# mainboardv0_1.net
KiCad netlist of a schematic drawn in EAGLE
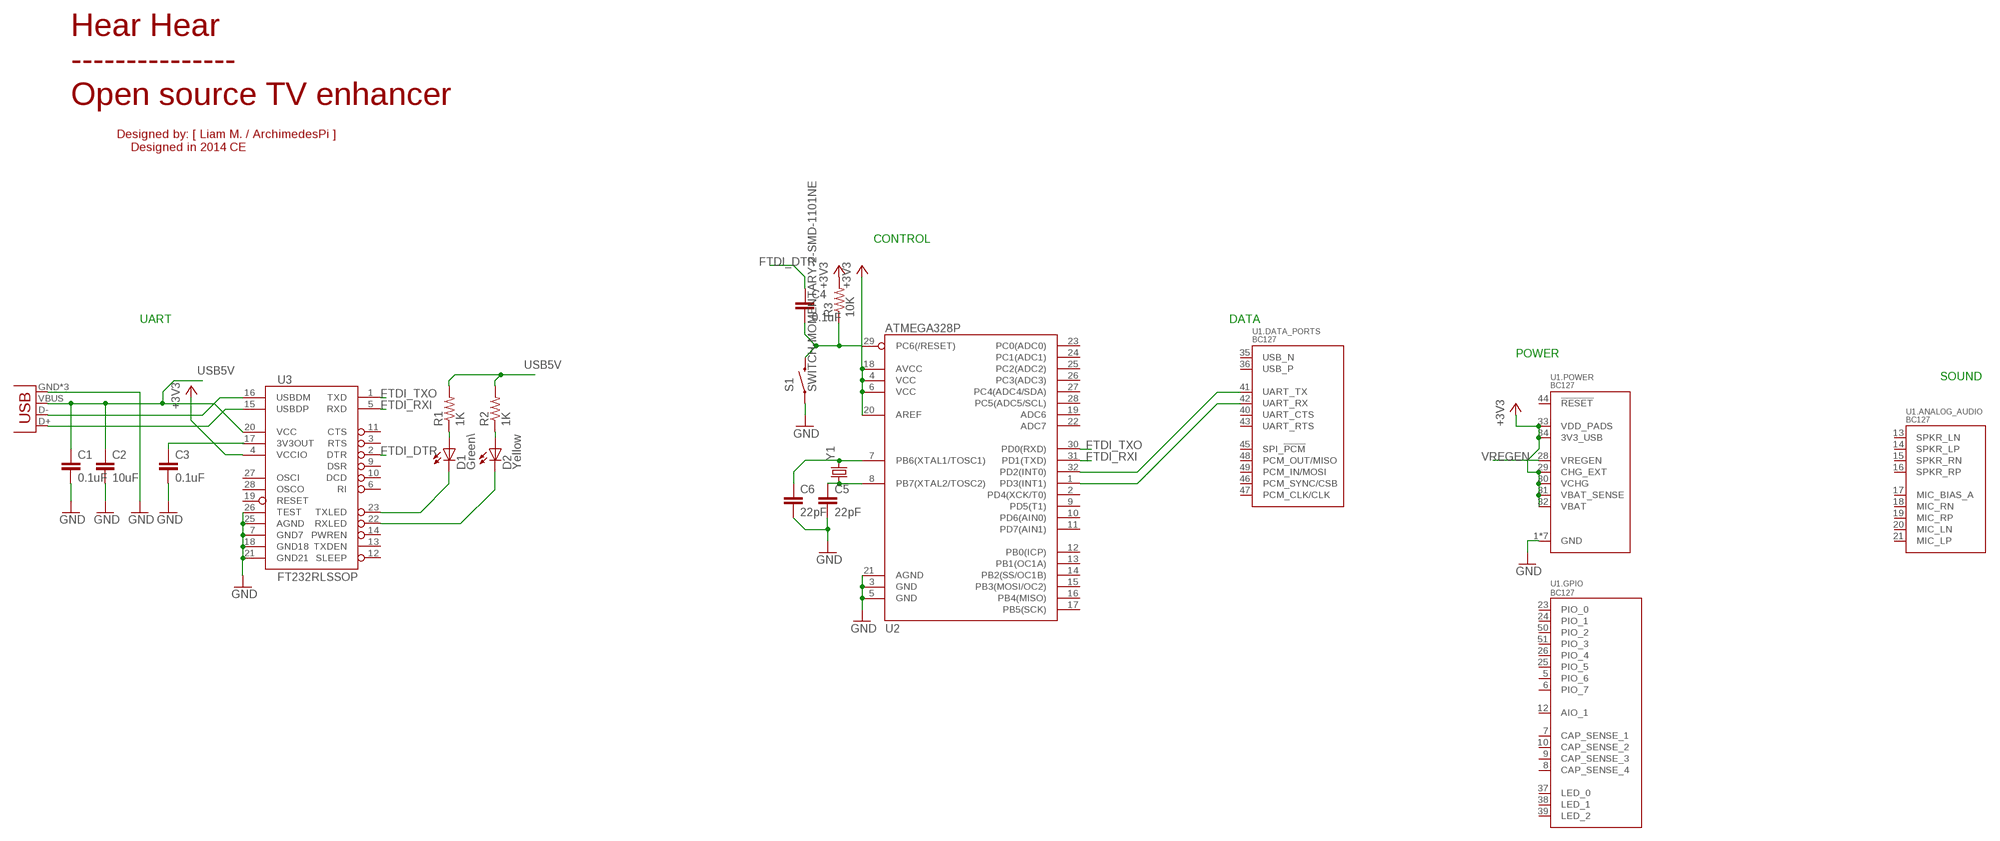
[diagram p0: schematic, sheet 1]

(export (version "E")
  (design (tool "Eeschema 10.0.6"))
  (components
    (comp (ref "C1")
      (value "0.1uF")
      (footprint "eagle-import:0603-CAP")
      (libsource (lib "eagle-import") (part "0.1UF-100V-10%(0603)"))
    )
    (comp (ref "C2")
      (value "10uF")
      (footprint "eagle-import:0603-CAP")
      (libsource (lib "eagle-import") (part "10UF-6.3V-20%(0603)"))
    )
    (comp (ref "C3")
      (value "0.1uF")
      (footprint "eagle-import:0603-CAP")
      (libsource (lib "eagle-import") (part "0.1UF-100V-10%(0603)"))
    )
    (comp (ref "C4")
      (value "0.1uF")
      (footprint "eagle-import:0603-CAP")
      (libsource (lib "eagle-import") (part "0.1UF-25V(+80/-20%)(0603)"))
    )
    (comp (ref "C5")
      (value "22pF")
      (footprint "eagle-import:0603-CAP")
      (libsource (lib "eagle-import") (part "22PF-50V-5%(0603)"))
    )
    (comp (ref "C6")
      (value "22pF")
      (footprint "eagle-import:0603-CAP")
      (libsource (lib "eagle-import") (part "22PF-50V-5%(0603)"))
    )
    (comp (ref "D1")
      (value "Green\\")
      (footprint "eagle-import:LED-0603")
      (libsource (lib "eagle-import") (part "LED-GREEN0603"))
    )
    (comp (ref "D2")
      (value "Yellow")
      (footprint "eagle-import:LED-0603")
      (libsource (lib "eagle-import") (part "LED-YELLOW0603"))
    )
    (comp (ref "JP1")
      (value "USB-MICROB")
      (footprint "eagle-import:USB-MICROB")
      (libsource (lib "eagle-import") (part "USB-MICROB"))
    )
    (comp (ref "R1")
      (value "1K")
      (footprint "eagle-import:0603-RES")
      (libsource (lib "eagle-import") (part "1KOHM1/10W1%(0603)"))
    )
    (comp (ref "R2")
      (value "1K")
      (footprint "eagle-import:0603-RES")
      (libsource (lib "eagle-import") (part "1KOHM1/10W1%(0603)"))
    )
    (comp (ref "R3")
      (value "10K")
      (footprint "eagle-import:0603-RES")
      (libsource (lib "eagle-import") (part "10KOHM1/10W1%(0603)0603"))
    )
    (comp (ref "S1")
      (value "SWITCH-MOMENTARY-2-SMD-1101NE")
      (footprint "eagle-import:TACTILE-SWITCH-1101NE")
      (libsource (lib "eagle-import") (part "SWITCH-MOMENTARY-2-SMD-1101NE"))
    )
    (comp (ref "U1")
      (value "BC127")
      (footprint "eagle-import:BC127")
      (libsource (lib "eagle-import") (part "BC127"))
    )
    (comp (ref "U2")
      (value "ATMEGA328P")
      (footprint "eagle-import:TQFP32-08")
      (libsource (lib "eagle-import") (part "ATMEGA328_SMT"))
    )
    (comp (ref "U3")
      (value "FT232RLSSOP")
      (footprint "eagle-import:SSOP28DB")
      (libsource (lib "eagle-import") (part "FT232RLSSOP"))
    )
    (comp (ref "Y1")
      (value "CRYSTALHC49US")
      (footprint "eagle-import:HC49US")
      (libsource (lib "eagle-import") (part "CRYSTALHC49US"))
    )
  )
  (nets
    (net (code "1") (name "+3V3") (class "Default")
      (node (ref "R3") (pin "2") (pinfunction "2_2") (pintype "passive"))
      (node (ref "U1") (pin "29") (pinfunction "CHG_EXT_29") (pintype "bidirectional"))
      (node (ref "U1") (pin "30") (pinfunction "VCHG_30") (pintype "bidirectional"))
      (node (ref "U1") (pin "31") (pinfunction "VBAT_SENSE_31") (pintype "bidirectional"))
      (node (ref "U1") (pin "32") (pinfunction "VBAT_32") (pintype "bidirectional"))
      (node (ref "U1") (pin "33") (pinfunction "VDD_PADS_33") (pintype "bidirectional"))
      (node (ref "U1") (pin "34") (pinfunction "3V3_USB_34") (pintype "bidirectional"))
      (node (ref "U2") (pin "18") (pinfunction "AVCC_18") (pintype "bidirectional"))
      (node (ref "U2") (pin "20") (pinfunction "AREF_20") (pintype "bidirectional"))
      (node (ref "U2") (pin "4") (pinfunction "VCC_4") (pintype "bidirectional"))
      (node (ref "U2") (pin "6") (pinfunction "VCC_6") (pintype "bidirectional"))
      (node (ref "U3") (pin "4") (pinfunction "VCCIO_4") (pintype "power_in"))
    )
    (net (code "2") (name "/FTDI_DTR") (class "Default")
      (node (ref "C4") (pin "1") (pinfunction "1_1") (pintype "passive"))
      (node (ref "U3") (pin "2") (pinfunction "DTR_2") (pintype "output"))
    )
    (net (code "3") (name "/FTDI_RXI") (class "Default")
      (node (ref "U2") (pin "31") (pinfunction "PD1(TXD)_31") (pintype "bidirectional"))
      (node (ref "U3") (pin "5") (pinfunction "RXD_5") (pintype "input"))
    )
    (net (code "4") (name "/FTDI_TXO") (class "Default")
      (node (ref "U2") (pin "30") (pinfunction "PD0(RXD)_30") (pintype "bidirectional"))
      (node (ref "U3") (pin "1") (pinfunction "TXD_1") (pintype "output"))
    )
    (net (code "5") (name "/USB5V") (class "Default")
      (node (ref "C1") (pin "1") (pinfunction "1_1") (pintype "passive"))
      (node (ref "C2") (pin "1") (pinfunction "1_1") (pintype "passive"))
      (node (ref "JP1") (pin "VBUS") (pinfunction "VBUS_VBUS") (pintype "bidirectional"))
      (node (ref "R1") (pin "2") (pinfunction "2_2") (pintype "passive"))
      (node (ref "R2") (pin "2") (pinfunction "2_2") (pintype "passive"))
      (node (ref "U3") (pin "20") (pinfunction "VCC_20") (pintype "power_in"))
    )
    (net (code "6") (name "/VREGEN") (class "Default")
      (node (ref "U1") (pin "28") (pinfunction "VREGEN_28") (pintype "bidirectional"))
    )
    (net (code "7") (name "GND") (class "Default")
      (node (ref "C1") (pin "2") (pinfunction "2_2") (pintype "passive"))
      (node (ref "C2") (pin "2") (pinfunction "2_2") (pintype "passive"))
      (node (ref "C3") (pin "2") (pinfunction "2_2") (pintype "passive"))
      (node (ref "C5") (pin "2") (pinfunction "2_2") (pintype "passive"))
      (node (ref "C6") (pin "2") (pinfunction "2_2") (pintype "passive"))
      (node (ref "JP1") (pin "GND") (pinfunction "GND_GND") (pintype "bidirectional"))
      (node (ref "JP1") (pin "MT1") (pinfunction "GND_MT1") (pintype "bidirectional"))
      (node (ref "JP1") (pin "MT2") (pinfunction "GND_MT2") (pintype "bidirectional"))
      (node (ref "S1") (pin "P$1") (pinfunction "1_P$1") (pintype "passive"))
      (node (ref "U1") (pin "1") (pinfunction "GND_1") (pintype "bidirectional"))
      (node (ref "U1") (pin "11") (pinfunction "GND_11") (pintype "bidirectional"))
      (node (ref "U1") (pin "2") (pinfunction "GND_2") (pintype "bidirectional"))
      (node (ref "U1") (pin "22") (pinfunction "GND_22") (pintype "bidirectional"))
      (node (ref "U1") (pin "27") (pinfunction "GND_27") (pintype "bidirectional"))
      (node (ref "U1") (pin "3") (pinfunction "GND_3") (pintype "bidirectional"))
      (node (ref "U1") (pin "4") (pinfunction "GND_4") (pintype "bidirectional"))
      (node (ref "U2") (pin "21") (pinfunction "AGND_21") (pintype "bidirectional"))
      (node (ref "U2") (pin "3") (pinfunction "GND_3") (pintype "bidirectional"))
      (node (ref "U2") (pin "5") (pinfunction "GND_5") (pintype "bidirectional"))
      (node (ref "U3") (pin "18") (pinfunction "GND18_18") (pintype "power_in"))
      (node (ref "U3") (pin "21") (pinfunction "GND21_21") (pintype "power_in"))
      (node (ref "U3") (pin "25") (pinfunction "AGND_25") (pintype "power_in"))
      (node (ref "U3") (pin "26") (pinfunction "TEST_26") (pintype "input"))
      (node (ref "U3") (pin "7") (pinfunction "GND7_7") (pintype "power_in"))
    )
    (net (code "8") (name "Net-(D1-PadA)") (class "Default")
      (node (ref "D1") (pin "A") (pinfunction "A_A") (pintype "passive"))
      (node (ref "R1") (pin "1") (pinfunction "1_1") (pintype "passive"))
    )
    (net (code "9") (name "Net-(D2-PadA)") (class "Default")
      (node (ref "D2") (pin "A") (pinfunction "A_A") (pintype "passive"))
      (node (ref "R2") (pin "1") (pinfunction "1_1") (pintype "passive"))
    )
    (net (code "10") (name "Net-(S1-2)") (class "Default")
      (node (ref "C4") (pin "2") (pinfunction "2_2") (pintype "passive"))
      (node (ref "R3") (pin "1") (pinfunction "1_1") (pintype "passive"))
      (node (ref "S1") (pin "P$2") (pinfunction "2_P$2") (pintype "passive"))
      (node (ref "U2") (pin "29") (pinfunction "PC6(/RESET)_29") (pintype "bidirectional"))
    )
    (net (code "11") (name "Net-(U1B-UART_RX)") (class "Default")
      (node (ref "U1") (pin "42") (pinfunction "UART_RX_42") (pintype "bidirectional"))
      (node (ref "U2") (pin "1") (pinfunction "PD3(INT1)_1") (pintype "bidirectional"))
    )
    (net (code "12") (name "Net-(U1B-UART_TX)") (class "Default")
      (node (ref "U1") (pin "41") (pinfunction "UART_TX_41") (pintype "bidirectional"))
      (node (ref "U2") (pin "32") (pinfunction "PD2(INT0)_32") (pintype "bidirectional"))
    )
    (net (code "13") (name "Net-(U2-PB6(XTAL1{slash}TOSC1))") (class "Default")
      (node (ref "C6") (pin "1") (pinfunction "1_1") (pintype "passive"))
      (node (ref "U2") (pin "7") (pinfunction "PB6(XTAL1/TOSC1)_7") (pintype "bidirectional"))
      (node (ref "Y1") (pin "2") (pinfunction "2_2") (pintype "passive"))
    )
    (net (code "14") (name "Net-(U2-PB7(XTAL2{slash}TOSC2))") (class "Default")
      (node (ref "C5") (pin "1") (pinfunction "1_1") (pintype "passive"))
      (node (ref "U2") (pin "8") (pinfunction "PB7(XTAL2/TOSC2)_8") (pintype "bidirectional"))
      (node (ref "Y1") (pin "1") (pinfunction "1_1") (pintype "passive"))
    )
    (net (code "15") (name "Net-(U3-3V3OUT)") (class "Default")
      (node (ref "C3") (pin "1") (pinfunction "1_1") (pintype "passive"))
      (node (ref "U3") (pin "17") (pinfunction "3V3OUT_17") (pintype "output"))
    )
    (net (code "16") (name "Net-(U3-RXLED)") (class "Default")
      (node (ref "D2") (pin "C") (pinfunction "C_C") (pintype "passive"))
      (node (ref "U3") (pin "22") (pinfunction "RXLED_22") (pintype "input"))
    )
    (net (code "17") (name "Net-(U3-TXLED)") (class "Default")
      (node (ref "D1") (pin "C") (pinfunction "C_C") (pintype "passive"))
      (node (ref "U3") (pin "23") (pinfunction "TXLED_23") (pintype "input"))
    )
    (net (code "18") (name "Net-(U3-USBDM)") (class "Default")
      (node (ref "JP1") (pin "D-") (pinfunction "D-_D-") (pintype "bidirectional"))
      (node (ref "U3") (pin "16") (pinfunction "USBDM_16") (pintype "bidirectional"))
    )
    (net (code "19") (name "Net-(U3-USBDP)") (class "Default")
      (node (ref "JP1") (pin "D+") (pinfunction "D+_D+") (pintype "bidirectional"))
      (node (ref "U3") (pin "15") (pinfunction "USBDP_15") (pintype "bidirectional"))
    )
    (net (code "20") (name "unconnected-(U1A-MIC_BIAS_A-Pad17)") (class "Default")
      (node (ref "U1") (pin "17") (pinfunction "MIC_BIAS_A_17") (pintype "bidirectional"))
    )
    (net (code "21") (name "unconnected-(U1A-MIC_LN-Pad20)") (class "Default")
      (node (ref "U1") (pin "20") (pinfunction "MIC_LN_20") (pintype "bidirectional"))
    )
    (net (code "22") (name "unconnected-(U1A-MIC_LP-Pad21)") (class "Default")
      (node (ref "U1") (pin "21") (pinfunction "MIC_LP_21") (pintype "bidirectional"))
    )
    (net (code "23") (name "unconnected-(U1A-MIC_RN-Pad18)") (class "Default")
      (node (ref "U1") (pin "18") (pinfunction "MIC_RN_18") (pintype "bidirectional"))
    )
    (net (code "24") (name "unconnected-(U1A-MIC_RP-Pad19)") (class "Default")
      (node (ref "U1") (pin "19") (pinfunction "MIC_RP_19") (pintype "bidirectional"))
    )
    (net (code "25") (name "unconnected-(U1A-SPKR_LN-Pad13)") (class "Default")
      (node (ref "U1") (pin "13") (pinfunction "SPKR_LN_13") (pintype "bidirectional"))
    )
    (net (code "26") (name "unconnected-(U1A-SPKR_LP-Pad14)") (class "Default")
      (node (ref "U1") (pin "14") (pinfunction "SPKR_LP_14") (pintype "bidirectional"))
    )
    (net (code "27") (name "unconnected-(U1A-SPKR_RN-Pad15)") (class "Default")
      (node (ref "U1") (pin "15") (pinfunction "SPKR_RN_15") (pintype "bidirectional"))
    )
    (net (code "28") (name "unconnected-(U1A-SPKR_RP-Pad16)") (class "Default")
      (node (ref "U1") (pin "16") (pinfunction "SPKR_RP_16") (pintype "bidirectional"))
    )
    (net (code "29") (name "unconnected-(U1B-PCM_CLK{slash}CLK-Pad47)") (class "Default")
      (node (ref "U1") (pin "47") (pinfunction "PCM_CLK/CLK_47") (pintype "bidirectional"))
    )
    (net (code "30") (name "unconnected-(U1B-PCM_IN{slash}MOSI-Pad49)") (class "Default")
      (node (ref "U1") (pin "49") (pinfunction "PCM_IN/MOSI_49") (pintype "bidirectional"))
    )
    (net (code "31") (name "unconnected-(U1B-PCM_OUT{slash}MISO-Pad48)") (class "Default")
      (node (ref "U1") (pin "48") (pinfunction "PCM_OUT/MISO_48") (pintype "bidirectional"))
    )
    (net (code "32") (name "unconnected-(U1B-PCM_SYNC{slash}CSB-Pad46)") (class "Default")
      (node (ref "U1") (pin "46") (pinfunction "PCM_SYNC/CSB_46") (pintype "bidirectional"))
    )
    (net (code "33") (name "unconnected-(U1B-SPI_~{PCM}-Pad45)") (class "Default")
      (node (ref "U1") (pin "45") (pinfunction "SPI_~{PCM}_45") (pintype "bidirectional"))
    )
    (net (code "34") (name "unconnected-(U1B-UART_CTS-Pad40)") (class "Default")
      (node (ref "U1") (pin "40") (pinfunction "UART_CTS_40") (pintype "bidirectional"))
    )
    (net (code "35") (name "unconnected-(U1B-UART_RTS-Pad43)") (class "Default")
      (node (ref "U1") (pin "43") (pinfunction "UART_RTS_43") (pintype "bidirectional"))
    )
    (net (code "36") (name "unconnected-(U1B-USB_N-Pad35)") (class "Default")
      (node (ref "U1") (pin "35") (pinfunction "USB_N_35") (pintype "bidirectional"))
    )
    (net (code "37") (name "unconnected-(U1B-USB_P-Pad36)") (class "Default")
      (node (ref "U1") (pin "36") (pinfunction "USB_P_36") (pintype "bidirectional"))
    )
    (net (code "38") (name "unconnected-(U1C-AIO_1-Pad12)") (class "Default")
      (node (ref "U1") (pin "12") (pinfunction "AIO_1_12") (pintype "bidirectional"))
    )
    (net (code "39") (name "unconnected-(U1C-CAP_SENSE_1-Pad7)") (class "Default")
      (node (ref "U1") (pin "7") (pinfunction "CAP_SENSE_1_7") (pintype "bidirectional"))
    )
    (net (code "40") (name "unconnected-(U1C-CAP_SENSE_2-Pad10)") (class "Default")
      (node (ref "U1") (pin "10") (pinfunction "CAP_SENSE_2_10") (pintype "bidirectional"))
    )
    (net (code "41") (name "unconnected-(U1C-CAP_SENSE_3-Pad9)") (class "Default")
      (node (ref "U1") (pin "9") (pinfunction "CAP_SENSE_3_9") (pintype "bidirectional"))
    )
    (net (code "42") (name "unconnected-(U1C-CAP_SENSE_4-Pad8)") (class "Default")
      (node (ref "U1") (pin "8") (pinfunction "CAP_SENSE_4_8") (pintype "bidirectional"))
    )
    (net (code "43") (name "unconnected-(U1C-LED_0-Pad37)") (class "Default")
      (node (ref "U1") (pin "37") (pinfunction "LED_0_37") (pintype "bidirectional"))
    )
    (net (code "44") (name "unconnected-(U1C-LED_1-Pad38)") (class "Default")
      (node (ref "U1") (pin "38") (pinfunction "LED_1_38") (pintype "bidirectional"))
    )
    (net (code "45") (name "unconnected-(U1C-LED_2-Pad39)") (class "Default")
      (node (ref "U1") (pin "39") (pinfunction "LED_2_39") (pintype "bidirectional"))
    )
    (net (code "46") (name "unconnected-(U1C-PIO_0-Pad23)") (class "Default")
      (node (ref "U1") (pin "23") (pinfunction "PIO_0_23") (pintype "bidirectional"))
    )
    (net (code "47") (name "unconnected-(U1C-PIO_1-Pad24)") (class "Default")
      (node (ref "U1") (pin "24") (pinfunction "PIO_1_24") (pintype "bidirectional"))
    )
    (net (code "48") (name "unconnected-(U1C-PIO_2-Pad50)") (class "Default")
      (node (ref "U1") (pin "50") (pinfunction "PIO_2_50") (pintype "bidirectional"))
    )
    (net (code "49") (name "unconnected-(U1C-PIO_3-Pad51)") (class "Default")
      (node (ref "U1") (pin "51") (pinfunction "PIO_3_51") (pintype "bidirectional"))
    )
    (net (code "50") (name "unconnected-(U1C-PIO_4-Pad26)") (class "Default")
      (node (ref "U1") (pin "26") (pinfunction "PIO_4_26") (pintype "bidirectional"))
    )
    (net (code "51") (name "unconnected-(U1C-PIO_5-Pad25)") (class "Default")
      (node (ref "U1") (pin "25") (pinfunction "PIO_5_25") (pintype "bidirectional"))
    )
    (net (code "52") (name "unconnected-(U1C-PIO_6-Pad5)") (class "Default")
      (node (ref "U1") (pin "5") (pinfunction "PIO_6_5") (pintype "bidirectional"))
    )
    (net (code "53") (name "unconnected-(U1C-PIO_7-Pad6)") (class "Default")
      (node (ref "U1") (pin "6") (pinfunction "PIO_7_6") (pintype "bidirectional"))
    )
    (net (code "54") (name "unconnected-(U1D-~{RESET}-Pad44)") (class "Default")
      (node (ref "U1") (pin "44") (pinfunction "~{RESET}_44") (pintype "bidirectional"))
    )
    (net (code "55") (name "unconnected-(U2-ADC6-Pad19)") (class "Default")
      (node (ref "U2") (pin "19") (pinfunction "ADC6_19") (pintype "bidirectional"))
    )
    (net (code "56") (name "unconnected-(U2-ADC7-Pad22)") (class "Default")
      (node (ref "U2") (pin "22") (pinfunction "ADC7_22") (pintype "bidirectional"))
    )
    (net (code "57") (name "unconnected-(U2-PB0(ICP)-Pad12)") (class "Default")
      (node (ref "U2") (pin "12") (pinfunction "PB0(ICP)_12") (pintype "bidirectional"))
    )
    (net (code "58") (name "unconnected-(U2-PB1(OC1A)-Pad13)") (class "Default")
      (node (ref "U2") (pin "13") (pinfunction "PB1(OC1A)_13") (pintype "bidirectional"))
    )
    (net (code "59") (name "unconnected-(U2-PB2(SS{slash}OC1B)-Pad14)") (class "Default")
      (node (ref "U2") (pin "14") (pinfunction "PB2(SS/OC1B)_14") (pintype "bidirectional"))
    )
    (net (code "60") (name "unconnected-(U2-PB3(MOSI{slash}OC2)-Pad15)") (class "Default")
      (node (ref "U2") (pin "15") (pinfunction "PB3(MOSI/OC2)_15") (pintype "bidirectional"))
    )
    (net (code "61") (name "unconnected-(U2-PB4(MISO)-Pad16)") (class "Default")
      (node (ref "U2") (pin "16") (pinfunction "PB4(MISO)_16") (pintype "bidirectional"))
    )
    (net (code "62") (name "unconnected-(U2-PB5(SCK)-Pad17)") (class "Default")
      (node (ref "U2") (pin "17") (pinfunction "PB5(SCK)_17") (pintype "bidirectional"))
    )
    (net (code "63") (name "unconnected-(U2-PC0(ADC0)-Pad23)") (class "Default")
      (node (ref "U2") (pin "23") (pinfunction "PC0(ADC0)_23") (pintype "bidirectional"))
    )
    (net (code "64") (name "unconnected-(U2-PC1(ADC1)-Pad24)") (class "Default")
      (node (ref "U2") (pin "24") (pinfunction "PC1(ADC1)_24") (pintype "bidirectional"))
    )
    (net (code "65") (name "unconnected-(U2-PC2(ADC2)-Pad25)") (class "Default")
      (node (ref "U2") (pin "25") (pinfunction "PC2(ADC2)_25") (pintype "bidirectional"))
    )
    (net (code "66") (name "unconnected-(U2-PC3(ADC3)-Pad26)") (class "Default")
      (node (ref "U2") (pin "26") (pinfunction "PC3(ADC3)_26") (pintype "bidirectional"))
    )
    (net (code "67") (name "unconnected-(U2-PC4(ADC4{slash}SDA)-Pad27)") (class "Default")
      (node (ref "U2") (pin "27") (pinfunction "PC4(ADC4/SDA)_27") (pintype "bidirectional"))
    )
    (net (code "68") (name "unconnected-(U2-PC5(ADC5{slash}SCL)-Pad28)") (class "Default")
      (node (ref "U2") (pin "28") (pinfunction "PC5(ADC5/SCL)_28") (pintype "bidirectional"))
    )
    (net (code "69") (name "unconnected-(U2-PD4(XCK{slash}T0)-Pad2)") (class "Default")
      (node (ref "U2") (pin "2") (pinfunction "PD4(XCK/T0)_2") (pintype "bidirectional"))
    )
    (net (code "70") (name "unconnected-(U2-PD5(T1)-Pad9)") (class "Default")
      (node (ref "U2") (pin "9") (pinfunction "PD5(T1)_9") (pintype "bidirectional"))
    )
    (net (code "71") (name "unconnected-(U2-PD6(AIN0)-Pad10)") (class "Default")
      (node (ref "U2") (pin "10") (pinfunction "PD6(AIN0)_10") (pintype "bidirectional"))
    )
    (net (code "72") (name "unconnected-(U2-PD7(AIN1)-Pad11)") (class "Default")
      (node (ref "U2") (pin "11") (pinfunction "PD7(AIN1)_11") (pintype "bidirectional"))
    )
    (net (code "73") (name "unconnected-(U3-CTS-Pad11)") (class "Default")
      (node (ref "U3") (pin "11") (pinfunction "CTS_11") (pintype "input"))
    )
    (net (code "74") (name "unconnected-(U3-DCD-Pad10)") (class "Default")
      (node (ref "U3") (pin "10") (pinfunction "DCD_10") (pintype "input"))
    )
    (net (code "75") (name "unconnected-(U3-DSR-Pad9)") (class "Default")
      (node (ref "U3") (pin "9") (pinfunction "DSR_9") (pintype "input"))
    )
    (net (code "76") (name "unconnected-(U3-OSCI-Pad27)") (class "Default")
      (node (ref "U3") (pin "27") (pinfunction "OSCI_27") (pintype "input"))
    )
    (net (code "77") (name "unconnected-(U3-OSCO-Pad28)") (class "Default")
      (node (ref "U3") (pin "28") (pinfunction "OSCO_28") (pintype "output"))
    )
    (net (code "78") (name "unconnected-(U3-PWREN-Pad14)") (class "Default")
      (node (ref "U3") (pin "14") (pinfunction "PWREN_14") (pintype "input"))
    )
    (net (code "79") (name "unconnected-(U3-RESET-Pad19)") (class "Default")
      (node (ref "U3") (pin "19") (pinfunction "RESET_19") (pintype "input"))
    )
    (net (code "80") (name "unconnected-(U3-RI-Pad6)") (class "Default")
      (node (ref "U3") (pin "6") (pinfunction "RI_6") (pintype "input"))
    )
    (net (code "81") (name "unconnected-(U3-RTS-Pad3)") (class "Default")
      (node (ref "U3") (pin "3") (pinfunction "RTS_3") (pintype "output"))
    )
    (net (code "82") (name "unconnected-(U3-SLEEP-Pad12)") (class "Default")
      (node (ref "U3") (pin "12") (pinfunction "SLEEP_12") (pintype "input"))
    )
    (net (code "83") (name "unconnected-(U3-TXDEN-Pad13)") (class "Default")
      (node (ref "U3") (pin "13") (pinfunction "TXDEN_13") (pintype "input"))
    )
  )
)
